# Yitran_IT900_Hutschiene_PIM7A_908_1_4_un.net
KiCad netlist of a schematic drawn in Altium Designer
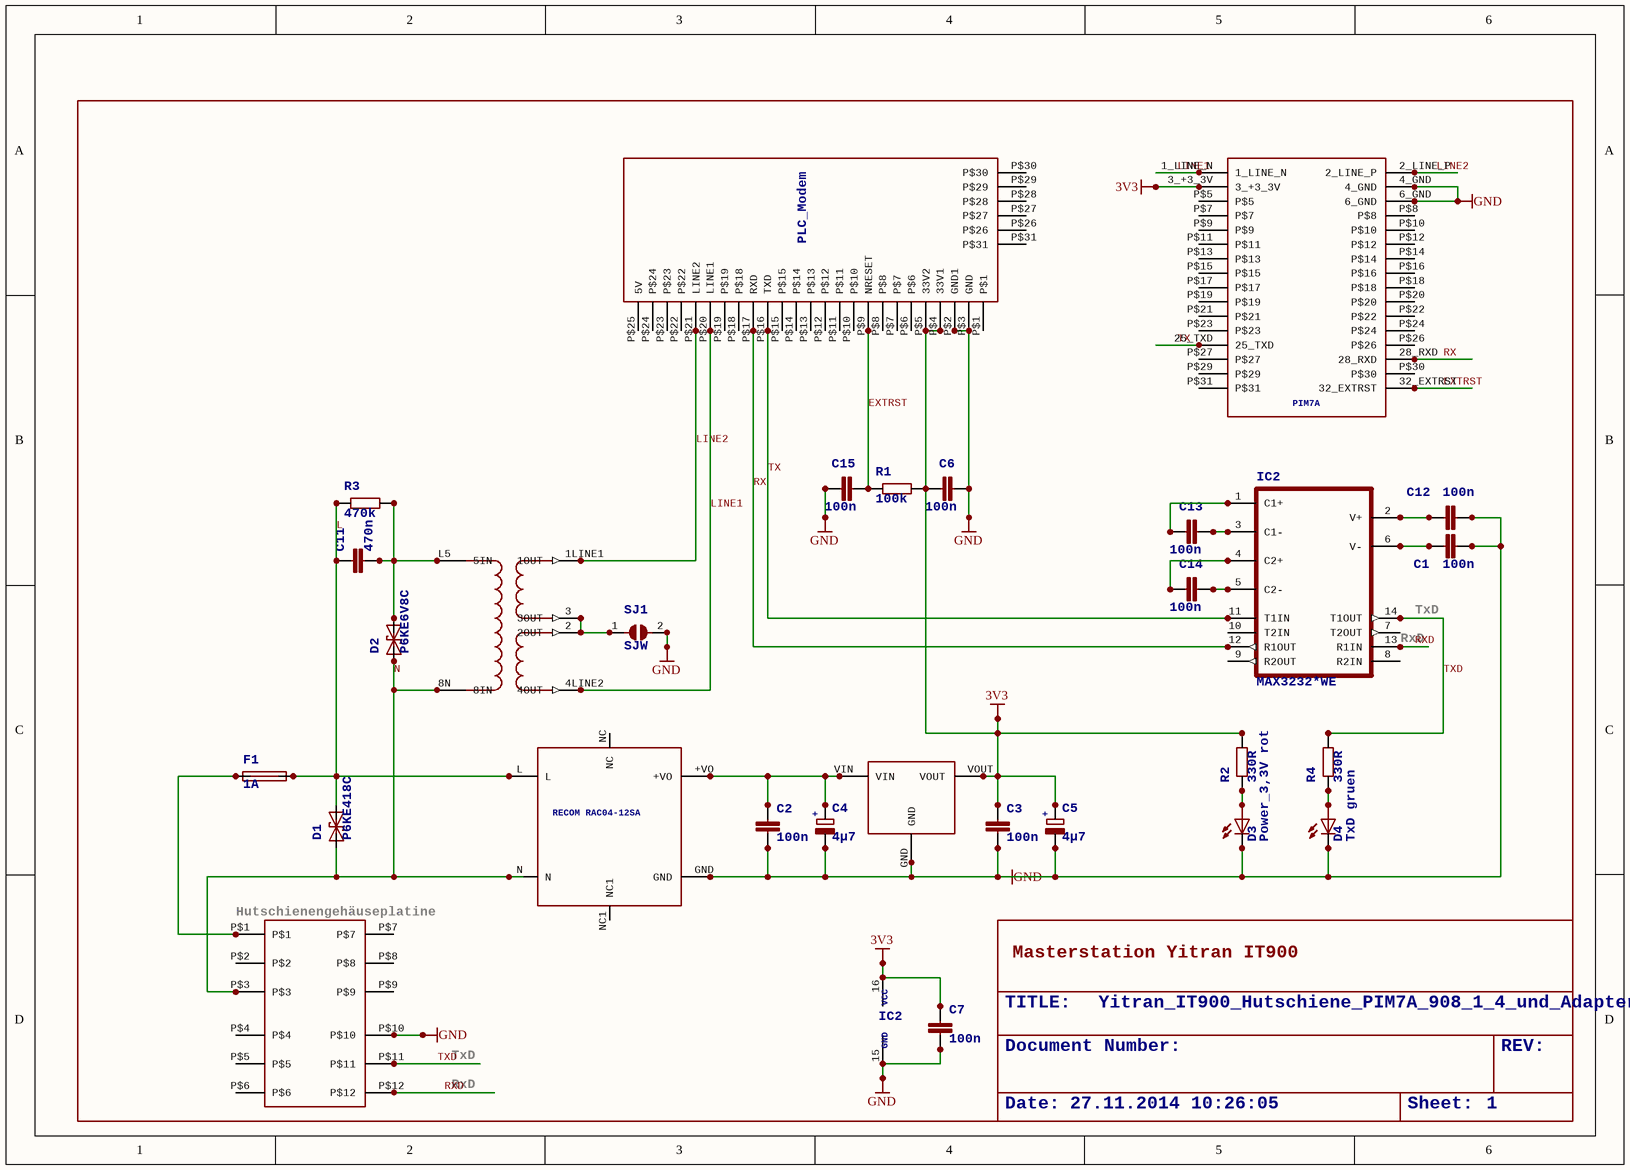
[diagram p0: Yitran_IT900_Hutschiene_PIM7A_908_1_4_und_Adapter_0.SchDoc]

(export (version "E")
  (design (tool "Eeschema 10.0.6"))
  (components
    (comp (ref "C1")
      (value "100n")
      (footprint "C1206K")
      (description "<B>CAPACITOR</B>, European symbol")
      (libsource (lib "") (part "C-EUC1206K_1"))
    )
    (comp (ref "C2")
      (value "100n")
      (footprint "C1206K")
      (description "<B>CAPACITOR</B>, European symbol")
      (fields (field (name ">NAME") "C2") (field (name ">VALUE") "100n"))
      (libsource (lib "resistor") (part "C-EUC1206K"))
    )
    (comp (ref "C3")
      (value "100n")
      (footprint "C1206K")
      (description "<B>CAPACITOR</B>, European symbol")
      (fields (field (name ">NAME") "C3") (field (name ">VALUE") "100n"))
      (libsource (lib "resistor") (part "C-EUC1206K"))
    )
    (comp (ref "C4")
      (value "4µ7")
      (footprint "E2,5-5")
      (description "<B>POLARIZED CAPACITOR</B>, European symbol")
      (fields (field (name ">NAME") "C4") (field (name "+") "+") (field (name ">VALUE") "4µ7"))
      (libsource (lib "resistor") (part "CPOL-EUE2.5-5"))
    )
    (comp (ref "C5")
      (value "4µ7")
      (footprint "E2,5-5")
      (description "<B>POLARIZED CAPACITOR</B>, European symbol")
      (fields (field (name ">NAME") "C5") (field (name "+") "+") (field (name ">VALUE") "4µ7"))
      (libsource (lib "resistor") (part "CPOL-EUE2.5-5"))
    )
    (comp (ref "C6")
      (value "100n")
      (footprint "C1206K")
      (description "<B>CAPACITOR</B>, European symbol")
      (libsource (lib "") (part "C-EUC1206K_1"))
    )
    (comp (ref "C7")
      (value "100n")
      (footprint "C1206K")
      (description "<B>CAPACITOR</B>, European symbol")
      (fields (field (name ">NAME") "C7") (field (name ">VALUE") "100n"))
      (libsource (lib "resistor") (part "C-EUC1206K"))
    )
    (comp (ref "C11")
      (value "470n")
      (footprint "C150-091X182")
      (description "<B>CAPACITOR</B>, European symbol")
      (fields (field (name ">NAME") "C11") (field (name ">VALUE") "470n"))
      (libsource (lib "resistor") (part "C-EU150-091X182"))
    )
    (comp (ref "C12")
      (value "100n")
      (footprint "C1206K")
      (description "<B>CAPACITOR</B>, European symbol")
      (libsource (lib "") (part "C-EUC1206K_1"))
    )
    (comp (ref "C13")
      (value "100n")
      (footprint "C1206K")
      (description "<B>CAPACITOR</B>, European symbol")
      (libsource (lib "") (part "C-EUC1206K_1"))
    )
    (comp (ref "C14")
      (value "100n")
      (footprint "C1206K")
      (description "<B>CAPACITOR</B>, European symbol")
      (libsource (lib "") (part "C-EUC1206K_1"))
    )
    (comp (ref "C15")
      (value "100n")
      (footprint "C1206K")
      (description "<B>CAPACITOR</B>, European symbol")
      (libsource (lib "") (part "C-EUC1206K_1"))
    )
    (comp (ref "D1")
      (value "P6KE418C")
      (footprint "CB417-15")
      (description "<B>DIODE</B><p>\ntransient-voltage suppressor")
      (fields (field (name ">NAME") "D1") (field (name ">VALUE") "P6KE418C"))
      (libsource (lib "diode") (part "P6KEXXC"))
    )
    (comp (ref "D2")
      (value "P6KE6V8C")
      (footprint "CB417-15")
      (description "<B>DIODE</B><p>\ntransient-voltage suppressor")
      (fields (field (name ">NAME") "D2") (field (name ">VALUE") "P6KE6V8C"))
      (libsource (lib "diode") (part "P6KEXXC"))
    )
    (comp (ref "D3")
      (value "Power_3,3V rot")
      (footprint "HLMP6")
      (description "<b>LED</b><p>\n2mm horizontal")
      (fields
        (field (name "MF") "AGILENT TECHNOLOGIES")
        (field (name "MPN") "HLMP-6500")
        (field (name ">NAME") "D3")
        (field (name ">VALUE") "Power_3,3V rot")
      )
      (libsource (lib "display-hp") (part "HLMP6"))
    )
    (comp (ref "D4")
      (value "TxD gruen")
      (footprint "HLMP6")
      (description "<b>LED</b><p>\n2mm horizontal")
      (fields
        (field (name "MF") "AGILENT TECHNOLOGIES")
        (field (name "MPN") "HLMP-6500")
        (field (name ">NAME") "D4")
        (field (name ">VALUE") "TxD gruen")
      )
      (libsource (lib "display-hp") (part "HLMP6"))
    )
    (comp (ref "F1")
      (value "1A")
      (footprint "TR5")
      (description "<b>FUSE</b><p>\nWickmann")
      (fields (field (name ">NAME") "F1") (field (name ">VALUE") "1A"))
      (libsource (lib "fuse") (part "TR5"))
    )
    (comp (ref "IC2")
      (value "MAX3232*WE")
      (footprint "SO16L")
      (fields
        (field (name "MPN") "MAX3232EWE+")
        (field (name ">NAME") "IC2")
        (field (name ">VALUE") "MAX3232*WE")
        (field (name "GND") "GND")
        (field (name "VCC") "VCC")
      )
      (libsource (lib "maxim") (part "MAX3232*WE"))
    )
    (comp (ref "R1")
      (value "100k")
      (footprint "M1406")
      (description "<B>RESISTOR</B>, European symbol")
      (fields (field (name ">NAME") "R1") (field (name ">VALUE") "100k"))
      (libsource (lib "resistor") (part "R-EU_M1406"))
    )
    (comp (ref "R2")
      (value "330R")
      (footprint "R1206")
      (description "<B>RESISTOR</B>, European symbol")
      (fields (field (name ">NAME") "R2") (field (name ">VALUE") "330R"))
      (libsource (lib "resistor") (part "R-EU_R1206"))
    )
    (comp (ref "R3")
      (value "470k")
      (footprint "0309/10")
      (description "<B>RESISTOR</B>, European symbol")
      (fields (field (name ">NAME") "R3") (field (name ">VALUE") "470k"))
      (libsource (lib "resistor") (part "R-EU_0309/10"))
    )
    (comp (ref "R4")
      (value "330R")
      (footprint "R1206")
      (description "<B>RESISTOR</B>, European symbol")
      (fields (field (name ">NAME") "R4") (field (name ">VALUE") "330R"))
      (libsource (lib "resistor") (part "R-EU_R1206"))
    )
    (comp (ref "SJ1")
      (value "SJW")
      (footprint "SJW")
      (description "SMD solder <b>JUMPER</b>")
      (fields (field (name ">NAME") "SJ1") (field (name ">VALUE") "SJW"))
      (libsource (lib "jumper") (part "SJW"))
    )
    (comp (ref "U$1")
      (value "RECOM_783_3")
      (footprint "RECOM785X")
      (libsource (lib "ADS") (part "RECOM_785_05"))
    )
    (comp (ref "U$2")
      (value "LDG-A-12")
      (footprint "LDG-A-12")
      (libsource (lib "Erni_LDG_A_12_Leiterplatte") (part "LDG-A-12"))
    )
    (comp (ref "U$3")
      (value "MODEMSTECKER")
      (footprint "MODEM_FUSS")
      (fields (field (name "PLC_MODEM") "PLC_Modem"))
      (libsource (lib "ADS") (part "MODEMSTECKER"))
    )
    (comp (ref "U$4")
      (value "IT900PIM7A")
      (footprint "IT900PIM7A")
      (fields (field (name "PIM7A") "PIM7A"))
      (libsource (lib "ADS1") (part "IT900PIM7A"))
    )
    (comp (ref "U$9")
      (value "RECOM_RAC04_12SA")
      (footprint "RAC04_12SA")
      (fields (field (name "RECOM RAC04-12SA") "RECOM RAC04-12SA"))
      (libsource (lib "ADS") (part "RECOM_RAC04_12SA"))
    )
    (comp (ref "U$10")
      (value "PLC_UEBERTRAGER_V2")
      (footprint "PLC-UEBERTRAGER_V2")
      (libsource (lib "ADS") (part "PLC_UEBERTRAGER_V2"))
    )
  )
  (nets
    (net (code "1") (name "/EXTRST") (class "Default")
      (node (ref "C15") (pin "2") (pinfunction "2_2") (pintype "passive"))
      (node (ref "R1") (pin "1") (pinfunction "1_1") (pintype "passive"))
      (node (ref "U$3") (pin "P$9") (pinfunction "NRESET_P$9") (pintype "passive"))
      (node (ref "U$4") (pin "32_EXTRST") (pinfunction "32_EXTRST_32_EXTRST") (pintype "passive"))
    )
    (net (code "2") (name "/L") (class "Default")
      (node (ref "C11") (pin "1") (pinfunction "1_1") (pintype "passive"))
      (node (ref "D1") (pin "C") (pinfunction "2_C") (pintype "passive"))
      (node (ref "F1") (pin "2") (pinfunction "2_2") (pintype "passive"))
      (node (ref "R3") (pin "1") (pinfunction "1_1") (pintype "passive"))
      (node (ref "U$9") (pin "L") (pinfunction "L_L") (pintype "passive"))
    )
    (net (code "3") (name "/LINE1") (class "Default")
      (node (ref "U$10") (pin "4LINE2") (pinfunction "4OUT_4LINE2") (pintype "output"))
      (node (ref "U$3") (pin "P$20") (pinfunction "LINE1_P$20") (pintype "passive"))
      (node (ref "U$4") (pin "1_LINE_N") (pinfunction "1_LINE_N_1_LINE_N") (pintype "passive"))
    )
    (net (code "4") (name "/LINE2") (class "Default")
      (node (ref "U$10") (pin "1LINE1") (pinfunction "1OUT_1LINE1") (pintype "output"))
      (node (ref "U$3") (pin "P$21") (pinfunction "LINE2_P$21") (pintype "passive"))
      (node (ref "U$4") (pin "2_LINE_P") (pinfunction "2_LINE_P_2_LINE_P") (pintype "passive"))
    )
    (net (code "5") (name "/N") (class "Default")
      (node (ref "D1") (pin "A") (pinfunction "1_A") (pintype "passive"))
      (node (ref "D2") (pin "A") (pinfunction "1_A") (pintype "passive"))
      (node (ref "U$10") (pin "8N") (pinfunction "8IN_8N") (pintype "passive"))
      (node (ref "U$2") (pin "P$3") (pinfunction "P$3_P$3") (pintype "passive"))
      (node (ref "U$9") (pin "N") (pinfunction "N_N") (pintype "passive"))
    )
    (net (code "6") (name "/RX") (class "Default")
      (node (ref "IC2") (pin "12") (pinfunction "R1OUT_12") (pintype "output"))
      (node (ref "U$3") (pin "P$17") (pinfunction "RXD_P$17") (pintype "passive"))
      (node (ref "U$4") (pin "28_RXD") (pinfunction "28_RXD_28_RXD") (pintype "passive"))
    )
    (net (code "7") (name "/RXD") (class "Default")
      (node (ref "IC2") (pin "13") (pinfunction "R1IN_13") (pintype "passive"))
      (node (ref "U$2") (pin "P$12") (pinfunction "P$12_P$12") (pintype "passive"))
    )
    (net (code "8") (name "/TX") (class "Default")
      (node (ref "IC2") (pin "11") (pinfunction "T1IN_11") (pintype "passive"))
      (node (ref "U$3") (pin "P$16") (pinfunction "TXD_P$16") (pintype "passive"))
      (node (ref "U$4") (pin "25_TXD") (pinfunction "25_TXD_25_TXD") (pintype "passive"))
    )
    (net (code "9") (name "/TXD") (class "Default")
      (node (ref "IC2") (pin "14") (pinfunction "T1OUT_14") (pintype "output"))
      (node (ref "R4") (pin "2") (pinfunction "2_2") (pintype "passive"))
      (node (ref "U$2") (pin "P$11") (pinfunction "P$11_P$11") (pintype "passive"))
    )
    (net (code "10") (name "3V3") (class "Default")
      (node (ref "C3") (pin "1") (pinfunction "1_1") (pintype "passive"))
      (node (ref "C5") (pin "+") (pinfunction "+_+") (pintype "passive"))
      (node (ref "C6") (pin "1") (pinfunction "1_1") (pintype "passive"))
      (node (ref "C7") (pin "1") (pinfunction "1_1") (pintype "passive"))
      (node (ref "IC2") (pin "16") (pinfunction "VCC_16") (pintype "power_in"))
      (node (ref "R1") (pin "2") (pinfunction "2_2") (pintype "passive"))
      (node (ref "R2") (pin "2") (pinfunction "2_2") (pintype "passive"))
      (node (ref "U$1") (pin "VOUT") (pinfunction "VOUT_VOUT") (pintype "passive"))
      (node (ref "U$3") (pin "P$4") (pinfunction "33V1_P$4") (pintype "passive"))
      (node (ref "U$3") (pin "P$5") (pinfunction "33V2_P$5") (pintype "passive"))
      (node (ref "U$4") (pin "3_+3_3V") (pinfunction "3_+3_3V_3_+3_3V") (pintype "passive"))
    )
    (net (code "11") (name "GND") (class "Default")
      (node (ref "C1") (pin "2") (pinfunction "2_2") (pintype "passive"))
      (node (ref "C12") (pin "2") (pinfunction "2_2") (pintype "passive"))
      (node (ref "C15") (pin "1") (pinfunction "1_1") (pintype "passive"))
      (node (ref "C2") (pin "2") (pinfunction "2_2") (pintype "passive"))
      (node (ref "C3") (pin "2") (pinfunction "2_2") (pintype "passive"))
      (node (ref "C4") (pin "-") (pinfunction "-_-") (pintype "passive"))
      (node (ref "C5") (pin "-") (pinfunction "-_-") (pintype "passive"))
      (node (ref "C6") (pin "2") (pinfunction "2_2") (pintype "passive"))
      (node (ref "C7") (pin "2") (pinfunction "2_2") (pintype "passive"))
      (node (ref "D3") (pin "K") (pinfunction "K_K") (pintype "passive"))
      (node (ref "D4") (pin "K") (pinfunction "K_K") (pintype "passive"))
      (node (ref "IC2") (pin "15") (pinfunction "GND_15") (pintype "power_in"))
      (node (ref "SJ1") (pin "2") (pinfunction "2_2") (pintype "passive"))
      (node (ref "U$1") (pin "GND") (pinfunction "GND_GND") (pintype "passive"))
      (node (ref "U$2") (pin "P$10") (pinfunction "P$10_P$10") (pintype "passive"))
      (node (ref "U$3") (pin "P$2") (pinfunction "GND1_P$2") (pintype "passive"))
      (node (ref "U$3") (pin "P$3") (pinfunction "GND_P$3") (pintype "passive"))
      (node (ref "U$4") (pin "4_GND") (pinfunction "4_GND_4_GND") (pintype "passive"))
      (node (ref "U$4") (pin "6_GND") (pinfunction "6_GND_6_GND") (pintype "passive"))
      (node (ref "U$9") (pin "GND") (pinfunction "GND_GND") (pintype "passive"))
    )
    (net (code "12") (name "Net-(C2-Pad1)") (class "Default")
      (node (ref "C2") (pin "1") (pinfunction "1_1") (pintype "passive"))
      (node (ref "C4") (pin "+") (pinfunction "+_+") (pintype "passive"))
      (node (ref "U$1") (pin "VIN") (pinfunction "VIN_VIN") (pintype "passive"))
      (node (ref "U$9") (pin "+VO") (pinfunction "+VO_+VO") (pintype "passive"))
    )
    (net (code "13") (name "Net-(D2-2)") (class "Default")
      (node (ref "C11") (pin "2") (pinfunction "2_2") (pintype "passive"))
      (node (ref "D2") (pin "C") (pinfunction "2_C") (pintype "passive"))
      (node (ref "R3") (pin "2") (pinfunction "2_2") (pintype "passive"))
      (node (ref "U$10") (pin "L5") (pinfunction "5IN_L5") (pintype "passive"))
    )
    (net (code "14") (name "Net-(D3-PadA)") (class "Default")
      (node (ref "D3") (pin "A") (pinfunction "A_A") (pintype "passive"))
      (node (ref "R2") (pin "1") (pinfunction "1_1") (pintype "passive"))
    )
    (net (code "15") (name "Net-(D4-PadA)") (class "Default")
      (node (ref "D4") (pin "A") (pinfunction "A_A") (pintype "passive"))
      (node (ref "R4") (pin "1") (pinfunction "1_1") (pintype "passive"))
    )
    (net (code "16") (name "Net-(F1-Pad1)") (class "Default")
      (node (ref "F1") (pin "1") (pinfunction "1_1") (pintype "passive"))
      (node (ref "U$2") (pin "P$1") (pinfunction "P$1_P$1") (pintype "passive"))
    )
    (net (code "17") (name "Net-(IC2A-C1+)") (class "Default")
      (node (ref "C13") (pin "1") (pinfunction "1_1") (pintype "passive"))
      (node (ref "IC2") (pin "1") (pinfunction "C1+_1") (pintype "passive"))
    )
    (net (code "18") (name "Net-(IC2A-C1-)") (class "Default")
      (node (ref "C13") (pin "2") (pinfunction "2_2") (pintype "passive"))
      (node (ref "IC2") (pin "3") (pinfunction "C1-_3") (pintype "passive"))
    )
    (net (code "19") (name "Net-(IC2A-C2+)") (class "Default")
      (node (ref "C14") (pin "1") (pinfunction "1_1") (pintype "passive"))
      (node (ref "IC2") (pin "4") (pinfunction "C2+_4") (pintype "passive"))
    )
    (net (code "20") (name "Net-(IC2A-C2-)") (class "Default")
      (node (ref "C14") (pin "2") (pinfunction "2_2") (pintype "passive"))
      (node (ref "IC2") (pin "5") (pinfunction "C2-_5") (pintype "passive"))
    )
    (net (code "21") (name "Net-(IC2A-V+)") (class "Default")
      (node (ref "C12") (pin "1") (pinfunction "1_1") (pintype "passive"))
      (node (ref "IC2") (pin "2") (pinfunction "V+_2") (pintype "passive"))
    )
    (net (code "22") (name "Net-(IC2A-V-)") (class "Default")
      (node (ref "C1") (pin "1") (pinfunction "1_1") (pintype "passive"))
      (node (ref "IC2") (pin "6") (pinfunction "V-_6") (pintype "passive"))
    )
    (net (code "23") (name "Net-(U$10-2OUT)") (class "Default")
      (node (ref "SJ1") (pin "1") (pinfunction "1_1") (pintype "passive"))
      (node (ref "U$10") (pin "2") (pinfunction "2OUT_2") (pintype "output"))
      (node (ref "U$10") (pin "3") (pinfunction "3OUT_3") (pintype "output"))
    )
    (net (code "24") (name "unconnected-(IC2A-R2IN-Pad8)") (class "Default")
      (node (ref "IC2") (pin "8") (pinfunction "R2IN_8") (pintype "passive"))
    )
    (net (code "25") (name "unconnected-(IC2A-R2OUT-Pad9)") (class "Default")
      (node (ref "IC2") (pin "9") (pinfunction "R2OUT_9") (pintype "output"))
    )
    (net (code "26") (name "unconnected-(IC2A-T2IN-Pad10)") (class "Default")
      (node (ref "IC2") (pin "10") (pinfunction "T2IN_10") (pintype "passive"))
    )
    (net (code "27") (name "unconnected-(IC2A-T2OUT-Pad7)") (class "Default")
      (node (ref "IC2") (pin "7") (pinfunction "T2OUT_7") (pintype "output"))
    )
    (net (code "28") (name "unconnected-(U$2-PadP$2)") (class "Default")
      (node (ref "U$2") (pin "P$2") (pinfunction "P$2_P$2") (pintype "passive"))
    )
    (net (code "29") (name "unconnected-(U$2-PadP$4)") (class "Default")
      (node (ref "U$2") (pin "P$4") (pinfunction "P$4_P$4") (pintype "passive"))
    )
    (net (code "30") (name "unconnected-(U$2-PadP$5)") (class "Default")
      (node (ref "U$2") (pin "P$5") (pinfunction "P$5_P$5") (pintype "passive"))
    )
    (net (code "31") (name "unconnected-(U$2-PadP$6)") (class "Default")
      (node (ref "U$2") (pin "P$6") (pinfunction "P$6_P$6") (pintype "passive"))
    )
    (net (code "32") (name "unconnected-(U$2-PadP$7)") (class "Default")
      (node (ref "U$2") (pin "P$7") (pinfunction "P$7_P$7") (pintype "passive"))
    )
    (net (code "33") (name "unconnected-(U$2-PadP$8)") (class "Default")
      (node (ref "U$2") (pin "P$8") (pinfunction "P$8_P$8") (pintype "passive"))
    )
    (net (code "34") (name "unconnected-(U$2-PadP$9)") (class "Default")
      (node (ref "U$2") (pin "P$9") (pinfunction "P$9_P$9") (pintype "passive"))
    )
    (net (code "35") (name "unconnected-(U$3-5V-PadP$25)") (class "Default")
      (node (ref "U$3") (pin "P$25") (pinfunction "5V_P$25") (pintype "passive"))
    )
    (net (code "36") (name "unconnected-(U$3-PadP$1)") (class "Default")
      (node (ref "U$3") (pin "P$1") (pinfunction "P$1_P$1") (pintype "passive"))
    )
    (net (code "37") (name "unconnected-(U$3-PadP$6)") (class "Default")
      (node (ref "U$3") (pin "P$6") (pinfunction "P$6_P$6") (pintype "passive"))
    )
    (net (code "38") (name "unconnected-(U$3-PadP$7)") (class "Default")
      (node (ref "U$3") (pin "P$7") (pinfunction "P$7_P$7") (pintype "passive"))
    )
    (net (code "39") (name "unconnected-(U$3-PadP$8)") (class "Default")
      (node (ref "U$3") (pin "P$8") (pinfunction "P$8_P$8") (pintype "passive"))
    )
    (net (code "40") (name "unconnected-(U$3-PadP$10)") (class "Default")
      (node (ref "U$3") (pin "P$10") (pinfunction "P$10_P$10") (pintype "passive"))
    )
    (net (code "41") (name "unconnected-(U$3-PadP$11)") (class "Default")
      (node (ref "U$3") (pin "P$11") (pinfunction "P$11_P$11") (pintype "passive"))
    )
    (net (code "42") (name "unconnected-(U$3-PadP$12)") (class "Default")
      (node (ref "U$3") (pin "P$12") (pinfunction "P$12_P$12") (pintype "passive"))
    )
    (net (code "43") (name "unconnected-(U$3-PadP$13)") (class "Default")
      (node (ref "U$3") (pin "P$13") (pinfunction "P$13_P$13") (pintype "passive"))
    )
    (net (code "44") (name "unconnected-(U$3-PadP$14)") (class "Default")
      (node (ref "U$3") (pin "P$14") (pinfunction "P$14_P$14") (pintype "passive"))
    )
    (net (code "45") (name "unconnected-(U$3-PadP$15)") (class "Default")
      (node (ref "U$3") (pin "P$15") (pinfunction "P$15_P$15") (pintype "passive"))
    )
    (net (code "46") (name "unconnected-(U$3-PadP$18)") (class "Default")
      (node (ref "U$3") (pin "P$18") (pinfunction "P$18_P$18") (pintype "passive"))
    )
    (net (code "47") (name "unconnected-(U$3-PadP$19)") (class "Default")
      (node (ref "U$3") (pin "P$19") (pinfunction "P$19_P$19") (pintype "passive"))
    )
    (net (code "48") (name "unconnected-(U$3-PadP$22)") (class "Default")
      (node (ref "U$3") (pin "P$22") (pinfunction "P$22_P$22") (pintype "passive"))
    )
    (net (code "49") (name "unconnected-(U$3-PadP$23)") (class "Default")
      (node (ref "U$3") (pin "P$23") (pinfunction "P$23_P$23") (pintype "passive"))
    )
    (net (code "50") (name "unconnected-(U$3-PadP$24)") (class "Default")
      (node (ref "U$3") (pin "P$24") (pinfunction "P$24_P$24") (pintype "passive"))
    )
    (net (code "51") (name "unconnected-(U$3-PadP$26)") (class "Default")
      (node (ref "U$3") (pin "P$26") (pinfunction "P$26_P$26") (pintype "passive"))
    )
    (net (code "52") (name "unconnected-(U$3-PadP$27)") (class "Default")
      (node (ref "U$3") (pin "P$27") (pinfunction "P$27_P$27") (pintype "passive"))
    )
    (net (code "53") (name "unconnected-(U$3-PadP$28)") (class "Default")
      (node (ref "U$3") (pin "P$28") (pinfunction "P$28_P$28") (pintype "passive"))
    )
    (net (code "54") (name "unconnected-(U$3-PadP$29)") (class "Default")
      (node (ref "U$3") (pin "P$29") (pinfunction "P$29_P$29") (pintype "passive"))
    )
    (net (code "55") (name "unconnected-(U$3-PadP$30)") (class "Default")
      (node (ref "U$3") (pin "P$30") (pinfunction "P$30_P$30") (pintype "passive"))
    )
    (net (code "56") (name "unconnected-(U$3-PadP$31)") (class "Default")
      (node (ref "U$3") (pin "P$31") (pinfunction "P$31_P$31") (pintype "passive"))
    )
    (net (code "57") (name "unconnected-(U$4-PadP$5)") (class "Default")
      (node (ref "U$4") (pin "P$5") (pinfunction "P$5_P$5") (pintype "passive"))
    )
    (net (code "58") (name "unconnected-(U$4-PadP$7)") (class "Default")
      (node (ref "U$4") (pin "P$7") (pinfunction "P$7_P$7") (pintype "passive"))
    )
    (net (code "59") (name "unconnected-(U$4-PadP$8)") (class "Default")
      (node (ref "U$4") (pin "P$8") (pinfunction "P$8_P$8") (pintype "passive"))
    )
    (net (code "60") (name "unconnected-(U$4-PadP$9)") (class "Default")
      (node (ref "U$4") (pin "P$9") (pinfunction "P$9_P$9") (pintype "passive"))
    )
    (net (code "61") (name "unconnected-(U$4-PadP$10)") (class "Default")
      (node (ref "U$4") (pin "P$10") (pinfunction "P$10_P$10") (pintype "passive"))
    )
    (net (code "62") (name "unconnected-(U$4-PadP$11)") (class "Default")
      (node (ref "U$4") (pin "P$11") (pinfunction "P$11_P$11") (pintype "passive"))
    )
    (net (code "63") (name "unconnected-(U$4-PadP$12)") (class "Default")
      (node (ref "U$4") (pin "P$12") (pinfunction "P$12_P$12") (pintype "passive"))
    )
    (net (code "64") (name "unconnected-(U$4-PadP$13)") (class "Default")
      (node (ref "U$4") (pin "P$13") (pinfunction "P$13_P$13") (pintype "passive"))
    )
    (net (code "65") (name "unconnected-(U$4-PadP$14)") (class "Default")
      (node (ref "U$4") (pin "P$14") (pinfunction "P$14_P$14") (pintype "passive"))
    )
    (net (code "66") (name "unconnected-(U$4-PadP$15)") (class "Default")
      (node (ref "U$4") (pin "P$15") (pinfunction "P$15_P$15") (pintype "passive"))
    )
    (net (code "67") (name "unconnected-(U$4-PadP$16)") (class "Default")
      (node (ref "U$4") (pin "P$16") (pinfunction "P$16_P$16") (pintype "passive"))
    )
    (net (code "68") (name "unconnected-(U$4-PadP$17)") (class "Default")
      (node (ref "U$4") (pin "P$17") (pinfunction "P$17_P$17") (pintype "passive"))
    )
    (net (code "69") (name "unconnected-(U$4-PadP$18)") (class "Default")
      (node (ref "U$4") (pin "P$18") (pinfunction "P$18_P$18") (pintype "passive"))
    )
    (net (code "70") (name "unconnected-(U$4-PadP$19)") (class "Default")
      (node (ref "U$4") (pin "P$19") (pinfunction "P$19_P$19") (pintype "passive"))
    )
    (net (code "71") (name "unconnected-(U$4-PadP$20)") (class "Default")
      (node (ref "U$4") (pin "P$20") (pinfunction "P$20_P$20") (pintype "passive"))
    )
    (net (code "72") (name "unconnected-(U$4-PadP$21)") (class "Default")
      (node (ref "U$4") (pin "P$21") (pinfunction "P$21_P$21") (pintype "passive"))
    )
    (net (code "73") (name "unconnected-(U$4-PadP$22)") (class "Default")
      (node (ref "U$4") (pin "P$22") (pinfunction "P$22_P$22") (pintype "passive"))
    )
    (net (code "74") (name "unconnected-(U$4-PadP$23)") (class "Default")
      (node (ref "U$4") (pin "P$23") (pinfunction "P$23_P$23") (pintype "passive"))
    )
    (net (code "75") (name "unconnected-(U$4-PadP$24)") (class "Default")
      (node (ref "U$4") (pin "P$24") (pinfunction "P$24_P$24") (pintype "passive"))
    )
    (net (code "76") (name "unconnected-(U$4-PadP$26)") (class "Default")
      (node (ref "U$4") (pin "P$26") (pinfunction "P$26_P$26") (pintype "passive"))
    )
    (net (code "77") (name "unconnected-(U$4-PadP$27)") (class "Default")
      (node (ref "U$4") (pin "P$27") (pinfunction "P$27_P$27") (pintype "passive"))
    )
    (net (code "78") (name "unconnected-(U$4-PadP$29)") (class "Default")
      (node (ref "U$4") (pin "P$29") (pinfunction "P$29_P$29") (pintype "passive"))
    )
    (net (code "79") (name "unconnected-(U$4-PadP$30)") (class "Default")
      (node (ref "U$4") (pin "P$30") (pinfunction "P$30_P$30") (pintype "passive"))
    )
    (net (code "80") (name "unconnected-(U$4-PadP$31)") (class "Default")
      (node (ref "U$4") (pin "P$31") (pinfunction "P$31_P$31") (pintype "passive"))
    )
    (net (code "81") (name "unconnected-(U$9-PadNC)") (class "Default")
      (node (ref "U$9") (pin "NC") (pinfunction "NC_NC") (pintype "passive"))
    )
    (net (code "82") (name "unconnected-(U$9-PadNC1)") (class "Default")
      (node (ref "U$9") (pin "NC1") (pinfunction "NC1_NC1") (pintype "passive"))
    )
  )
)
